# SX1308_GTW_e381v02c_STM32_MCU.net
KiCad netlist of a schematic drawn in Altium Designer
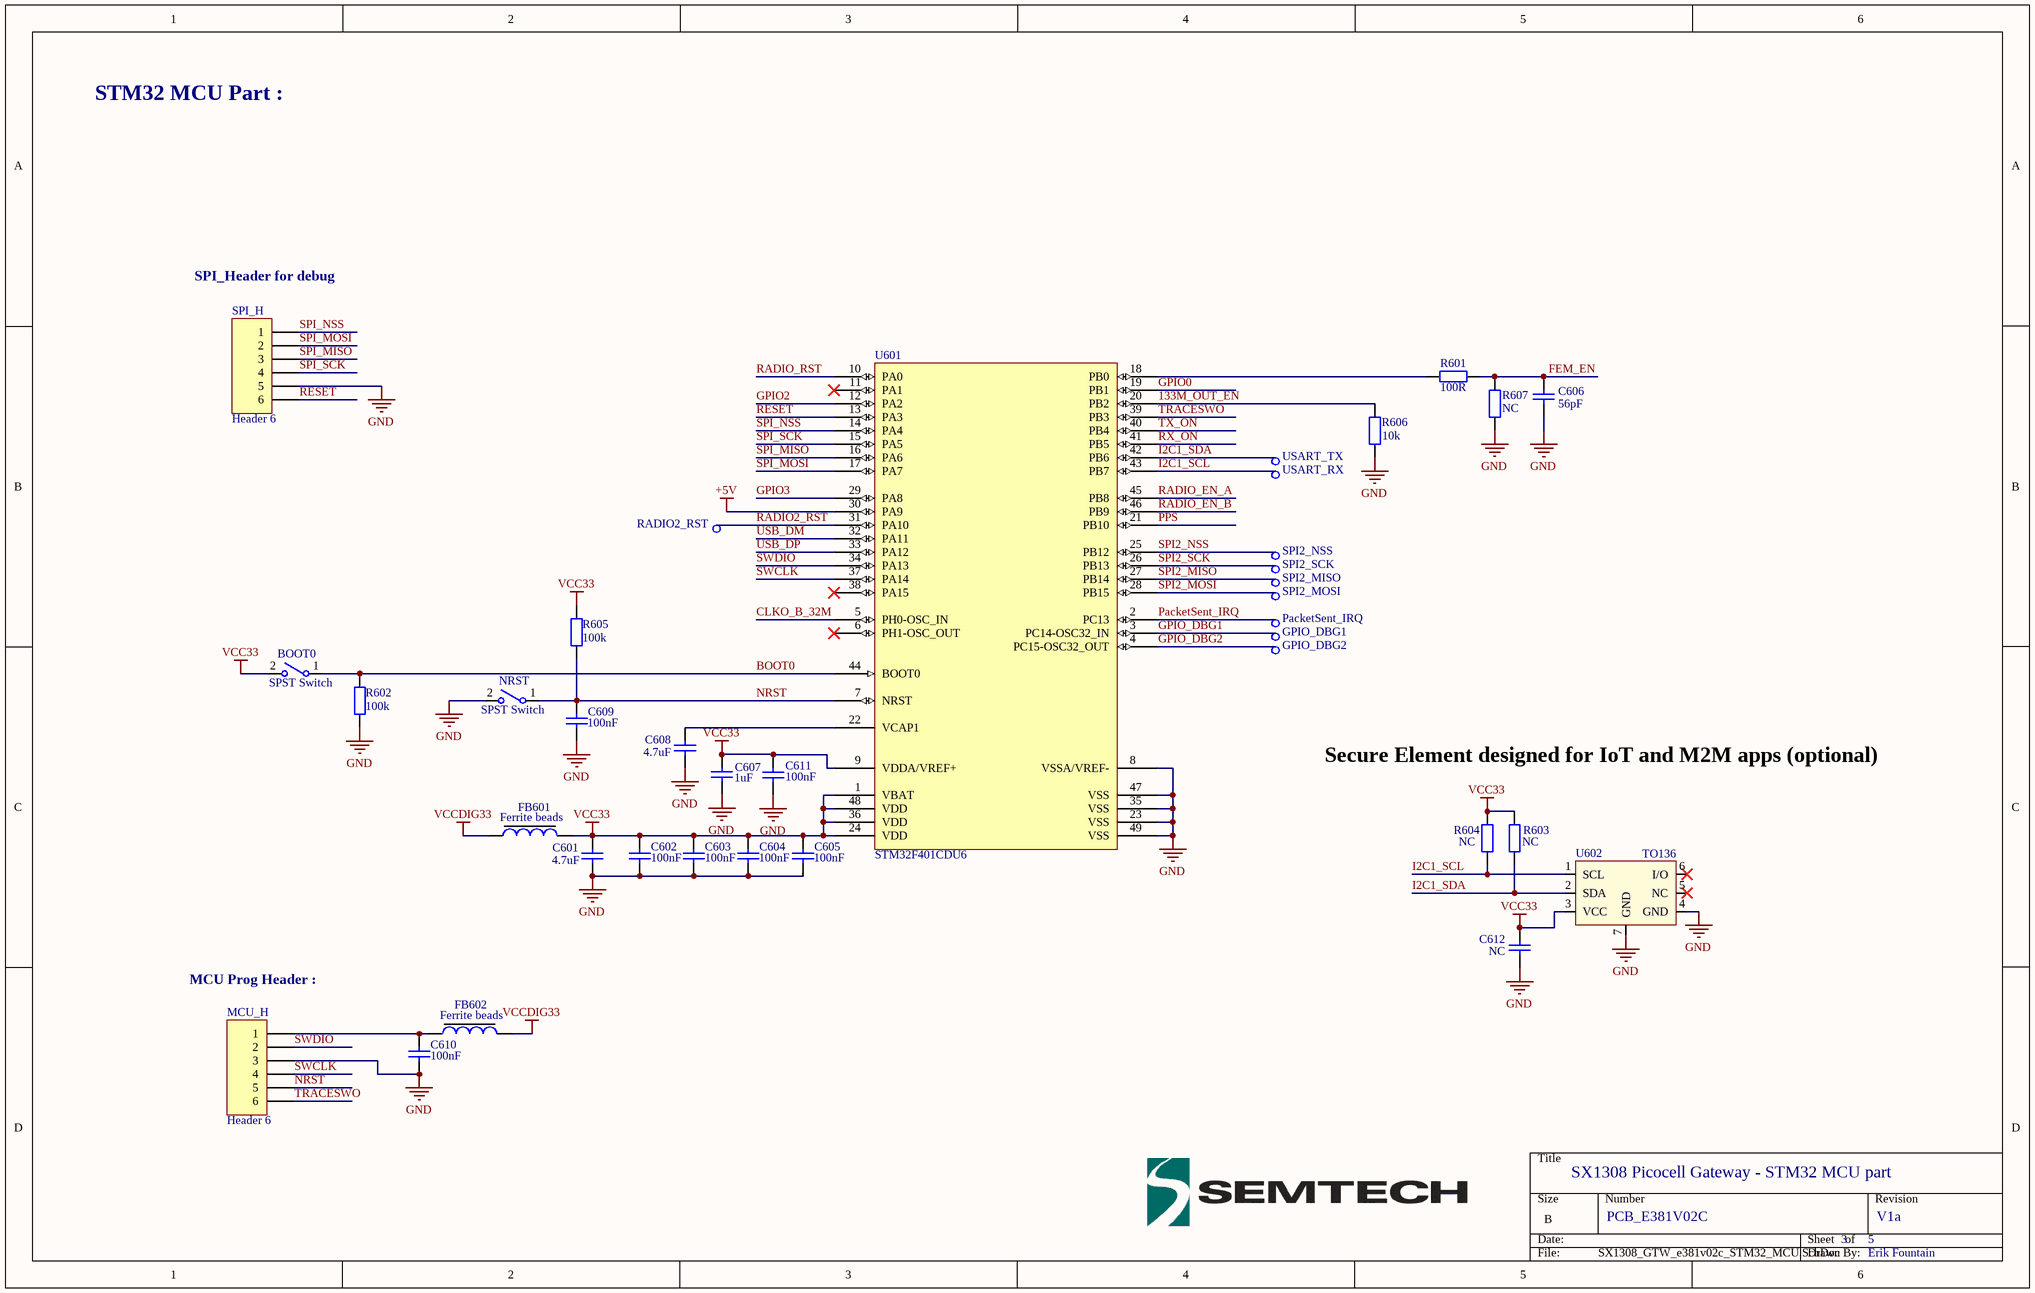
[diagram p0: SX1308_GTW_e381v02c_STM32_MCU.SchDoc]

(export (version "E")
  (design (tool "Eeschema 10.0.6"))
  (components
    (comp (ref "BOOT0")
      (value "SPST Switch")
      (footprint "KXT_series_switch_3.5x2.0mm")
      (description "SPST, N.O. - Tactile Switch")
      (libsource (lib "SX1308_GTW_e381v02c") (part "SW-SPST"))
    )
    (comp (ref "C601")
      (value "4.7uF")
      (footprint "rlc_603_smd")
      (description "Capacitor SMD")
      (fields (field (name "Comment") "Cap") (field (name "PUBLISHER") "Altium Limited"))
      (libsource (lib "SX1308_GTW_e381v02c") (part "Cap"))
    )
    (comp (ref "C602")
      (value "100nF")
      (footprint "rlc_402_smd")
      (description "Capacitor SMD")
      (fields (field (name "Comment") "Cap") (field (name "PUBLISHER") "Altium Limited"))
      (libsource (lib "SX1308_GTW_e381v02c") (part "Cap"))
    )
    (comp (ref "C603")
      (value "100nF")
      (footprint "rlc_402_smd")
      (description "Capacitor SMD")
      (fields (field (name "Comment") "Cap") (field (name "PUBLISHER") "Altium Limited"))
      (libsource (lib "SX1308_GTW_e381v02c") (part "Cap"))
    )
    (comp (ref "C604")
      (value "100nF")
      (footprint "rlc_402_smd")
      (description "Capacitor SMD")
      (fields (field (name "Comment") "Cap") (field (name "PUBLISHER") "Altium Limited"))
      (libsource (lib "SX1308_GTW_e381v02c") (part "Cap"))
    )
    (comp (ref "C605")
      (value "100nF")
      (footprint "rlc_402_smd")
      (description "Capacitor SMD")
      (fields (field (name "Comment") "Cap") (field (name "PUBLISHER") "Altium Limited"))
      (libsource (lib "SX1308_GTW_e381v02c") (part "Cap"))
    )
    (comp (ref "C606")
      (value "56pF")
      (footprint "rlc_402_smd")
      (description "Capacitor SMD")
      (fields (field (name "Comment") "Cap") (field (name "PUBLISHER") "Altium Limited"))
      (libsource (lib "SX1308_GTW_e381v02c") (part "Cap"))
    )
    (comp (ref "C607")
      (value "1uF")
      (footprint "rlc_402_smd")
      (description "Capacitor SMD")
      (fields (field (name "Comment") "Cap") (field (name "PUBLISHER") "Altium Limited"))
      (libsource (lib "SX1308_GTW_e381v02c") (part "Cap"))
    )
    (comp (ref "C608")
      (value "4.7uF")
      (footprint "rlc_603_smd")
      (description "Capacitor SMD")
      (fields (field (name "Comment") "Cap") (field (name "PUBLISHER") "Altium Limited"))
      (libsource (lib "SX1308_GTW_e381v02c") (part "Cap"))
    )
    (comp (ref "C609")
      (value "100nF")
      (footprint "rlc_402_smd")
      (description "Capacitor SMD")
      (fields (field (name "Comment") "Cap") (field (name "PUBLISHER") "Altium Limited"))
      (libsource (lib "SX1308_GTW_e381v02c") (part "Cap"))
    )
    (comp (ref "C610")
      (value "100nF")
      (footprint "rlc_402_smd")
      (description "Capacitor SMD")
      (fields (field (name "Comment") "Cap") (field (name "PUBLISHER") "Altium Limited"))
      (libsource (lib "SX1308_GTW_e381v02c") (part "Cap"))
    )
    (comp (ref "C611")
      (value "100nF")
      (footprint "rlc_402_smd")
      (description "Capacitor SMD")
      (fields (field (name "Comment") "Cap") (field (name "PUBLISHER") "Altium Limited"))
      (libsource (lib "SX1308_GTW_e381v02c") (part "Cap"))
    )
    (comp (ref "C612")
      (value "NC")
      (footprint "rlc_402_smd")
      (description "Capacitor SMD")
      (fields (field (name "Comment") "Cap") (field (name "PUBLISHER") "Altium Limited"))
      (libsource (lib "SX1308_GTW_e381v02c") (part "Cap"))
    )
    (comp (ref "FB601")
      (value "Ferrite beads")
      (footprint "rlc_402_smd")
      (libsource (lib "SX1308_GTW_e381v02c") (part "Ferrite beads"))
    )
    (comp (ref "FB602")
      (value "Ferrite beads")
      (footprint "rlc_402_smd")
      (libsource (lib "SX1308_GTW_e381v02c") (part "Ferrite beads"))
    )
    (comp (ref "GPIO_DBG1")
      (value "Test Pin")
      (footprint "PIN_SMD")
      (libsource (lib "SX1308_GTW_e381v02c") (part "test_pin"))
    )
    (comp (ref "GPIO_DBG2")
      (value "Test Pin")
      (footprint "PIN_SMD")
      (libsource (lib "SX1308_GTW_e381v02c") (part "test_pin"))
    )
    (comp (ref "MCU_H")
      (value "Header 6")
      (footprint "HDR1X6_SMD")
      (description "Header, 6-Pin")
      (fields (field (name "PUBLISHER") "Altium Limited"))
      (libsource (lib "SX1308_GTW_e381v02c") (part "Header 6"))
    )
    (comp (ref "NRST")
      (value "SPST Switch")
      (footprint "KXT_series_switch_3.5x2.0mm")
      (description "SPST, N.O. - Tactile Switch")
      (libsource (lib "SX1308_GTW_e381v02c") (part "SW-SPST"))
    )
    (comp (ref "PacketSent_IRQ")
      (value "Test Pin")
      (footprint "PIN_SMD")
      (libsource (lib "SX1308_GTW_e381v02c") (part "test_pin"))
    )
    (comp (ref "R601")
      (value "100R")
      (footprint "rlc_402_smd")
      (description "Resistor SMD - IEC symbol version")
      (fields (field (name "Comment") "Resistor"))
      (libsource (lib "SX1308_GTW_e381v02c") (part "Resistor"))
    )
    (comp (ref "R602")
      (value "100k")
      (footprint "rlc_402_smd")
      (description "Resistor SMD - IEC symbol version")
      (fields (field (name "Comment") "Resistor"))
      (libsource (lib "") (part "Resistor_1"))
    )
    (comp (ref "R603")
      (value "NC")
      (footprint "rlc_201_smd")
      (description "Resistor SMD - IEC symbol version")
      (fields (field (name "Comment") "Resistor"))
      (libsource (lib "SX1308_GTW_e381v02c") (part "Resistor"))
    )
    (comp (ref "R604")
      (value "NC")
      (footprint "rlc_201_smd")
      (description "Resistor SMD - IEC symbol version")
      (fields (field (name "Comment") "Resistor"))
      (libsource (lib "SX1308_GTW_e381v02c") (part "Resistor"))
    )
    (comp (ref "R605")
      (value "100k")
      (footprint "rlc_402_smd")
      (description "Resistor SMD - IEC symbol version")
      (fields (field (name "Comment") "Resistor"))
      (libsource (lib "") (part "Resistor_1"))
    )
    (comp (ref "R606")
      (value "10k")
      (footprint "rlc_402_smd")
      (description "Resistor SMD - IEC symbol version")
      (fields (field (name "Comment") "Resistor"))
      (libsource (lib "") (part "Resistor_1"))
    )
    (comp (ref "R607")
      (value "NC")
      (footprint "rlc_402_smd")
      (description "Resistor SMD - IEC symbol version")
      (fields (field (name "Comment") "Resistor"))
      (libsource (lib "") (part "Resistor_1"))
    )
    (comp (ref "RADIO2_RST")
      (value "Test Pin")
      (footprint "PIN_SMD")
      (libsource (lib "SX1308_GTW_e381v02c") (part "test_pin"))
    )
    (comp (ref "SPI2_MISO")
      (value "Test Pin")
      (footprint "PIN_SMD")
      (libsource (lib "SX1308_GTW_e381v02c") (part "test_pin"))
    )
    (comp (ref "SPI2_MOSI")
      (value "Test Pin")
      (footprint "PIN_SMD")
      (libsource (lib "SX1308_GTW_e381v02c") (part "test_pin"))
    )
    (comp (ref "SPI2_NSS")
      (value "Test Pin")
      (footprint "PIN_SMD")
      (libsource (lib "SX1308_GTW_e381v02c") (part "test_pin"))
    )
    (comp (ref "SPI2_SCK")
      (value "Test Pin")
      (footprint "PIN_SMD")
      (libsource (lib "SX1308_GTW_e381v02c") (part "test_pin"))
    )
    (comp (ref "SPI_H")
      (value "Header 6")
      (footprint "HDR1X6_SMD")
      (description "Header, 6-Pin")
      (fields (field (name "PUBLISHER") "Altium Limited"))
      (libsource (lib "SX1308_GTW_e381v02c") (part "Header 6"))
    )
    (comp (ref "U601")
      (value "STM32F401CDU6")
      (footprint "UFQFPN48_7x7MM")
      (description "STM32 ARM Cortex M4 32-bit MCU with 256Kbytes Flash/96kB RAM, UFQFPN48 package")
      (libsource (lib "SX1308_GTW_e381v02c") (part "STM32F401CDU6"))
    )
    (comp (ref "U602")
      (value "TO136")
      (footprint "DFN6_3X3mm")
      (description "TO136 - Secure Element designed for IoT and M2M applications.")
      (libsource (lib "SX1308_GTW_e381v02c") (part "TO136"))
    )
    (comp (ref "USART_RX")
      (value "Test Pin")
      (footprint "PIN_SMD")
      (libsource (lib "SX1308_GTW_e381v02c") (part "test_pin"))
    )
    (comp (ref "USART_TX")
      (value "Test Pin")
      (footprint "PIN_SMD")
      (libsource (lib "SX1308_GTW_e381v02c") (part "test_pin"))
    )
  )
  (nets
    (net (code "1") (name "+5V") (class "Default")
      (node (ref "U601") (pin "30") (pinfunction "PA9_30") (pintype "bidirectional"))
    )
    (net (code "2") (name "/133M_OUT_EN") (class "Default")
      (node (ref "R606") (pin "2") (pinfunction "2_2") (pintype "passive"))
      (node (ref "U601") (pin "20") (pinfunction "PB2_20") (pintype "bidirectional"))
    )
    (net (code "3") (name "/BOOT0") (class "Default")
      (node (ref "BOOT0") (pin "1") (pinfunction "COMMON_1") (pintype "passive"))
      (node (ref "R602") (pin "2") (pinfunction "2_2") (pintype "passive"))
      (node (ref "U601") (pin "44") (pinfunction "BOOT0_44") (pintype "input"))
    )
    (net (code "4") (name "/CLKO_B_32M") (class "Default")
      (node (ref "U601") (pin "5") (pinfunction "PH0-OSC_IN_5") (pintype "bidirectional"))
    )
    (net (code "5") (name "/FEM_EN") (class "Default")
      (node (ref "C606") (pin "2") (pinfunction "2_2") (pintype "passive"))
      (node (ref "R601") (pin "2") (pinfunction "2_2") (pintype "passive"))
      (node (ref "R607") (pin "2") (pinfunction "2_2") (pintype "passive"))
    )
    (net (code "6") (name "/GPIO0") (class "Default")
      (node (ref "U601") (pin "19") (pinfunction "PB1_19") (pintype "bidirectional"))
    )
    (net (code "7") (name "/GPIO2") (class "Default")
      (node (ref "U601") (pin "12") (pinfunction "PA2_12") (pintype "bidirectional"))
    )
    (net (code "8") (name "/GPIO3") (class "Default")
      (node (ref "U601") (pin "29") (pinfunction "PA8_29") (pintype "bidirectional"))
    )
    (net (code "9") (name "/GPIO_DBG1") (class "Default")
      (node (ref "GPIO_DBG1") (pin "1") (pinfunction "pin_1") (pintype "passive"))
      (node (ref "U601") (pin "3") (pinfunction "PC14-OSC32_IN_3") (pintype "bidirectional"))
    )
    (net (code "10") (name "/GPIO_DBG2") (class "Default")
      (node (ref "GPIO_DBG2") (pin "1") (pinfunction "pin_1") (pintype "passive"))
      (node (ref "U601") (pin "4") (pinfunction "PC15-OSC32_OUT_4") (pintype "bidirectional"))
    )
    (net (code "11") (name "/I2C1_SCL") (class "Default")
      (node (ref "R604") (pin "1") (pinfunction "1_1") (pintype "passive"))
      (node (ref "U601") (pin "43") (pinfunction "PB7_43") (pintype "bidirectional"))
      (node (ref "U602") (pin "1") (pinfunction "SCL_1") (pintype "passive"))
      (node (ref "USART_RX") (pin "1") (pinfunction "pin_1") (pintype "passive"))
    )
    (net (code "12") (name "/I2C1_SDA") (class "Default")
      (node (ref "R603") (pin "1") (pinfunction "1_1") (pintype "passive"))
      (node (ref "U601") (pin "42") (pinfunction "PB6_42") (pintype "bidirectional"))
      (node (ref "U602") (pin "2") (pinfunction "SDA_2") (pintype "passive"))
      (node (ref "USART_TX") (pin "1") (pinfunction "pin_1") (pintype "passive"))
    )
    (net (code "13") (name "/NRST") (class "Default")
      (node (ref "C609") (pin "2") (pinfunction "2_2") (pintype "passive"))
      (node (ref "MCU_H") (pin "5") (pinfunction "5_5") (pintype "passive"))
      (node (ref "NRST") (pin "1") (pinfunction "COMMON_1") (pintype "passive"))
      (node (ref "R605") (pin "1") (pinfunction "1_1") (pintype "passive"))
      (node (ref "U601") (pin "7") (pinfunction "NRST_7") (pintype "bidirectional"))
    )
    (net (code "14") (name "/PPS") (class "Default")
      (node (ref "U601") (pin "21") (pinfunction "PB10_21") (pintype "bidirectional"))
    )
    (net (code "15") (name "/PacketSent_IRQ") (class "Default")
      (node (ref "PacketSent_IRQ") (pin "1") (pinfunction "pin_1") (pintype "passive"))
      (node (ref "U601") (pin "2") (pinfunction "PC13_2") (pintype "bidirectional"))
    )
    (net (code "16") (name "/RADIO2_RST") (class "Default")
      (node (ref "RADIO2_RST") (pin "1") (pinfunction "pin_1") (pintype "passive"))
      (node (ref "U601") (pin "31") (pinfunction "PA10_31") (pintype "bidirectional"))
    )
    (net (code "17") (name "/RADIO_EN_A") (class "Default")
      (node (ref "U601") (pin "45") (pinfunction "PB8_45") (pintype "bidirectional"))
    )
    (net (code "18") (name "/RADIO_EN_B") (class "Default")
      (node (ref "U601") (pin "46") (pinfunction "PB9_46") (pintype "bidirectional"))
    )
    (net (code "19") (name "/RADIO_RST") (class "Default")
      (node (ref "U601") (pin "10") (pinfunction "PA0_10") (pintype "bidirectional"))
    )
    (net (code "20") (name "/RESET") (class "Default")
      (node (ref "SPI_H") (pin "6") (pinfunction "6_6") (pintype "passive"))
      (node (ref "U601") (pin "13") (pinfunction "PA3_13") (pintype "bidirectional"))
    )
    (net (code "21") (name "/RX_ON") (class "Default")
      (node (ref "U601") (pin "41") (pinfunction "PB5_41") (pintype "bidirectional"))
    )
    (net (code "22") (name "/SPI2_MISO") (class "Default")
      (node (ref "SPI2_MISO") (pin "1") (pinfunction "pin_1") (pintype "passive"))
      (node (ref "U601") (pin "27") (pinfunction "PB14_27") (pintype "bidirectional"))
    )
    (net (code "23") (name "/SPI2_MOSI") (class "Default")
      (node (ref "SPI2_MOSI") (pin "1") (pinfunction "pin_1") (pintype "passive"))
      (node (ref "U601") (pin "28") (pinfunction "PB15_28") (pintype "bidirectional"))
    )
    (net (code "24") (name "/SPI2_NSS") (class "Default")
      (node (ref "SPI2_NSS") (pin "1") (pinfunction "pin_1") (pintype "passive"))
      (node (ref "U601") (pin "25") (pinfunction "PB12_25") (pintype "bidirectional"))
    )
    (net (code "25") (name "/SPI2_SCK") (class "Default")
      (node (ref "SPI2_SCK") (pin "1") (pinfunction "pin_1") (pintype "passive"))
      (node (ref "U601") (pin "26") (pinfunction "PB13_26") (pintype "bidirectional"))
    )
    (net (code "26") (name "/SPI_MISO") (class "Default")
      (node (ref "SPI_H") (pin "3") (pinfunction "3_3") (pintype "passive"))
      (node (ref "U601") (pin "16") (pinfunction "PA6_16") (pintype "bidirectional"))
    )
    (net (code "27") (name "/SPI_MOSI") (class "Default")
      (node (ref "SPI_H") (pin "2") (pinfunction "2_2") (pintype "passive"))
      (node (ref "U601") (pin "17") (pinfunction "PA7_17") (pintype "bidirectional"))
    )
    (net (code "28") (name "/SPI_NSS") (class "Default")
      (node (ref "SPI_H") (pin "1") (pinfunction "1_1") (pintype "passive"))
      (node (ref "U601") (pin "14") (pinfunction "PA4_14") (pintype "bidirectional"))
    )
    (net (code "29") (name "/SPI_SCK") (class "Default")
      (node (ref "SPI_H") (pin "4") (pinfunction "4_4") (pintype "passive"))
      (node (ref "U601") (pin "15") (pinfunction "PA5_15") (pintype "bidirectional"))
    )
    (net (code "30") (name "/SWCLK") (class "Default")
      (node (ref "MCU_H") (pin "4") (pinfunction "4_4") (pintype "passive"))
      (node (ref "U601") (pin "37") (pinfunction "PA14_37") (pintype "bidirectional"))
    )
    (net (code "31") (name "/SWDIO") (class "Default")
      (node (ref "MCU_H") (pin "2") (pinfunction "2_2") (pintype "passive"))
      (node (ref "U601") (pin "34") (pinfunction "PA13_34") (pintype "bidirectional"))
    )
    (net (code "32") (name "/TRACESWO") (class "Default")
      (node (ref "MCU_H") (pin "6") (pinfunction "6_6") (pintype "passive"))
      (node (ref "U601") (pin "39") (pinfunction "PB3_39") (pintype "bidirectional"))
    )
    (net (code "33") (name "/TX_ON") (class "Default")
      (node (ref "U601") (pin "40") (pinfunction "PB4_40") (pintype "bidirectional"))
    )
    (net (code "34") (name "/USB_DM") (class "Default")
      (node (ref "U601") (pin "32") (pinfunction "PA11_32") (pintype "bidirectional"))
    )
    (net (code "35") (name "/USB_DP") (class "Default")
      (node (ref "U601") (pin "33") (pinfunction "PA12_33") (pintype "bidirectional"))
    )
    (net (code "36") (name "GND") (class "Default")
      (node (ref "C601") (pin "1") (pinfunction "1_1") (pintype "passive"))
      (node (ref "C602") (pin "1") (pinfunction "1_1") (pintype "passive"))
      (node (ref "C603") (pin "1") (pinfunction "1_1") (pintype "passive"))
      (node (ref "C604") (pin "1") (pinfunction "1_1") (pintype "passive"))
      (node (ref "C605") (pin "1") (pinfunction "1_1") (pintype "passive"))
      (node (ref "C606") (pin "1") (pinfunction "1_1") (pintype "passive"))
      (node (ref "C607") (pin "1") (pinfunction "1_1") (pintype "passive"))
      (node (ref "C608") (pin "1") (pinfunction "1_1") (pintype "passive"))
      (node (ref "C609") (pin "1") (pinfunction "1_1") (pintype "passive"))
      (node (ref "C610") (pin "1") (pinfunction "1_1") (pintype "passive"))
      (node (ref "C611") (pin "1") (pinfunction "1_1") (pintype "passive"))
      (node (ref "C612") (pin "1") (pinfunction "1_1") (pintype "passive"))
      (node (ref "MCU_H") (pin "3") (pinfunction "3_3") (pintype "passive"))
      (node (ref "NRST") (pin "2") (pinfunction "NO_2") (pintype "passive"))
      (node (ref "R602") (pin "1") (pinfunction "1_1") (pintype "passive"))
      (node (ref "R606") (pin "1") (pinfunction "1_1") (pintype "passive"))
      (node (ref "R607") (pin "1") (pinfunction "1_1") (pintype "passive"))
      (node (ref "SPI_H") (pin "5") (pinfunction "5_5") (pintype "passive"))
      (node (ref "U601") (pin "23") (pinfunction "VSS_23") (pintype "power_in"))
      (node (ref "U601") (pin "35") (pinfunction "VSS_35") (pintype "power_in"))
      (node (ref "U601") (pin "47") (pinfunction "VSS_47") (pintype "power_in"))
      (node (ref "U601") (pin "49") (pinfunction "VSS_49") (pintype "power_in"))
      (node (ref "U601") (pin "8") (pinfunction "VSSA/VREF-_8") (pintype "power_in"))
      (node (ref "U602") (pin "4") (pinfunction "GND_4") (pintype "passive"))
      (node (ref "U602") (pin "7") (pinfunction "GND_7") (pintype "passive"))
    )
    (net (code "37") (name "Net-(C610-Pad2)") (class "Default")
      (node (ref "C610") (pin "2") (pinfunction "2_2") (pintype "passive"))
      (node (ref "FB602") (pin "1") (pinfunction "1_1") (pintype "passive"))
      (node (ref "MCU_H") (pin "1") (pinfunction "1_1") (pintype "passive"))
    )
    (net (code "38") (name "Net-(U601-PB0)") (class "Default")
      (node (ref "R601") (pin "1") (pinfunction "1_1") (pintype "passive"))
      (node (ref "U601") (pin "18") (pinfunction "PB0_18") (pintype "bidirectional"))
    )
    (net (code "39") (name "Net-(U601-VCAP1)") (class "Default")
      (node (ref "C608") (pin "2") (pinfunction "2_2") (pintype "passive"))
      (node (ref "U601") (pin "22") (pinfunction "VCAP1_22") (pintype "power_in"))
    )
    (net (code "40") (name "VCC33") (class "Default")
      (node (ref "BOOT0") (pin "2") (pinfunction "NO_2") (pintype "passive"))
      (node (ref "C601") (pin "2") (pinfunction "2_2") (pintype "passive"))
      (node (ref "C602") (pin "2") (pinfunction "2_2") (pintype "passive"))
      (node (ref "C603") (pin "2") (pinfunction "2_2") (pintype "passive"))
      (node (ref "C604") (pin "2") (pinfunction "2_2") (pintype "passive"))
      (node (ref "C605") (pin "2") (pinfunction "2_2") (pintype "passive"))
      (node (ref "C607") (pin "2") (pinfunction "2_2") (pintype "passive"))
      (node (ref "C611") (pin "2") (pinfunction "2_2") (pintype "passive"))
      (node (ref "C612") (pin "2") (pinfunction "2_2") (pintype "passive"))
      (node (ref "FB601") (pin "2") (pinfunction "2_2") (pintype "passive"))
      (node (ref "R603") (pin "2") (pinfunction "2_2") (pintype "passive"))
      (node (ref "R604") (pin "2") (pinfunction "2_2") (pintype "passive"))
      (node (ref "R605") (pin "2") (pinfunction "2_2") (pintype "passive"))
      (node (ref "U601") (pin "1") (pinfunction "VBAT_1") (pintype "power_in"))
      (node (ref "U601") (pin "24") (pinfunction "VDD_24") (pintype "power_in"))
      (node (ref "U601") (pin "36") (pinfunction "VDD_36") (pintype "power_in"))
      (node (ref "U601") (pin "48") (pinfunction "VDD_48") (pintype "power_in"))
      (node (ref "U601") (pin "9") (pinfunction "VDDA/VREF+_9") (pintype "power_in"))
      (node (ref "U602") (pin "3") (pinfunction "VCC_3") (pintype "passive"))
    )
    (net (code "41") (name "VCCDIG33") (class "Default")
      (node (ref "FB601") (pin "1") (pinfunction "1_1") (pintype "passive"))
      (node (ref "FB602") (pin "2") (pinfunction "2_2") (pintype "passive"))
    )
    (net (code "42") (name "unconnected-(U601-PA1-Pad11)") (class "Default")
      (node (ref "U601") (pin "11") (pinfunction "PA1_11") (pintype "bidirectional+no_connect"))
    )
    (net (code "43") (name "unconnected-(U601-PA15-Pad38)") (class "Default")
      (node (ref "U601") (pin "38") (pinfunction "PA15_38") (pintype "bidirectional+no_connect"))
    )
    (net (code "44") (name "unconnected-(U601-PH1-OSC_OUT-Pad6)") (class "Default")
      (node (ref "U601") (pin "6") (pinfunction "PH1-OSC_OUT_6") (pintype "bidirectional+no_connect"))
    )
    (net (code "45") (name "unconnected-(U602-I{slash}O-Pad6)") (class "Default")
      (node (ref "U602") (pin "6") (pinfunction "I/O_6") (pintype "passive+no_connect"))
    )
    (net (code "46") (name "unconnected-(U602-NC-Pad5)") (class "Default")
      (node (ref "U602") (pin "5") (pinfunction "NC_5") (pintype "passive+no_connect"))
    )
  )
)
